# 02_Filtr2.net
KiCad netlist of a schematic drawn in Altium Designer
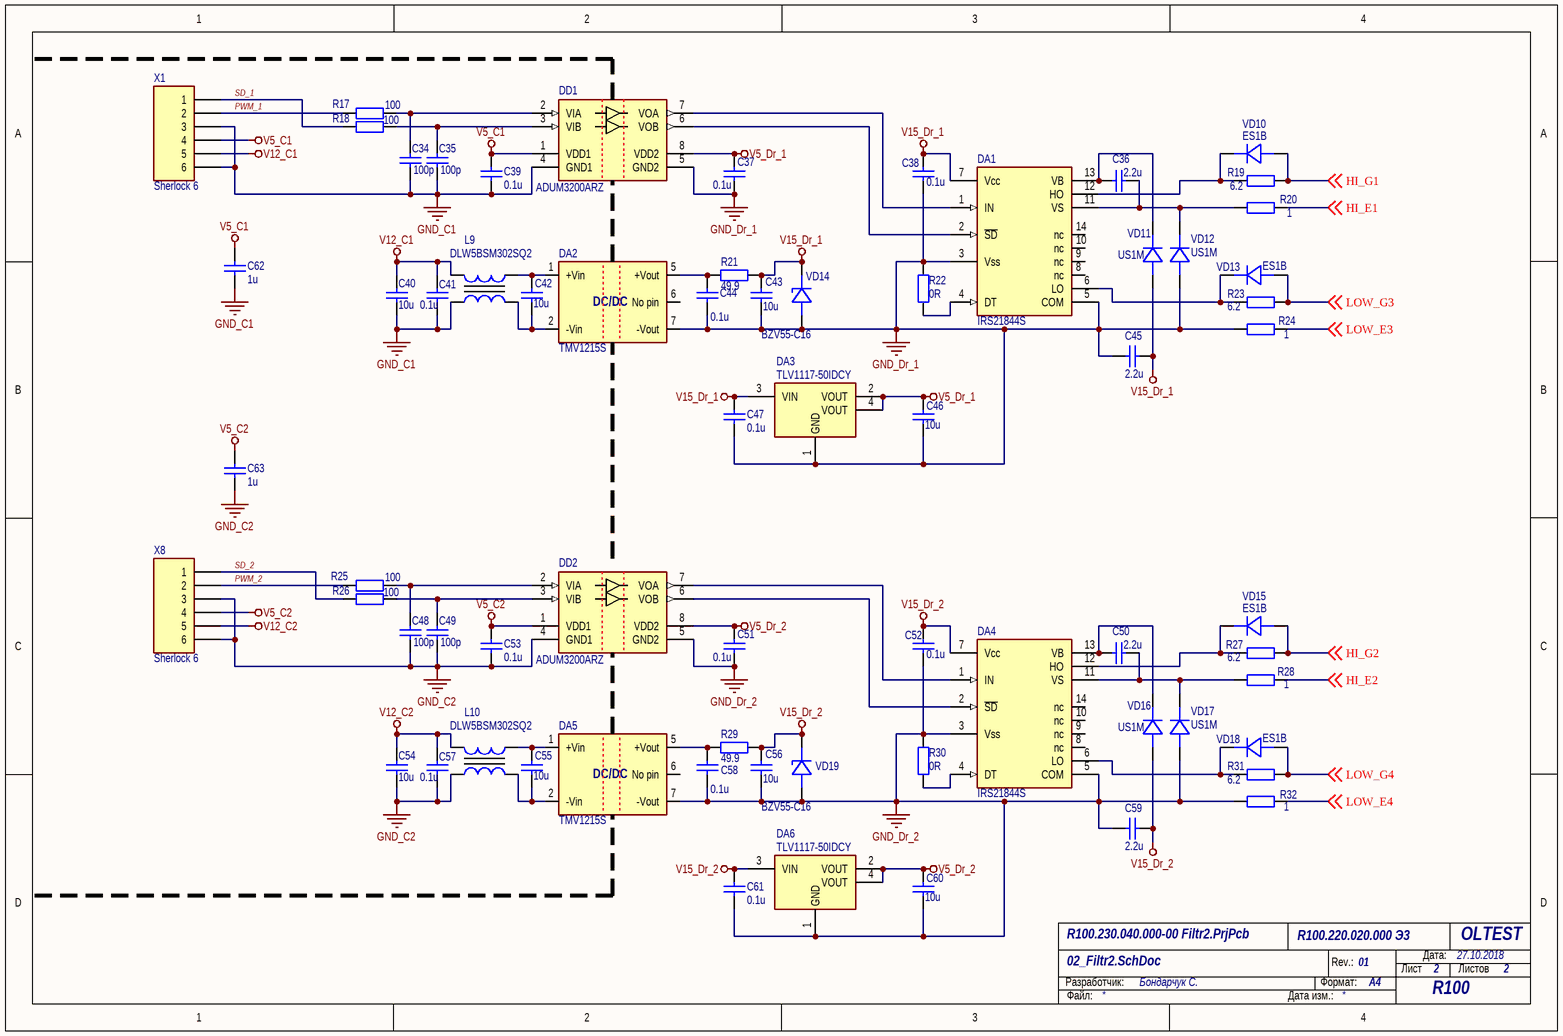
[diagram p0: 02_Filtr2.SchDoc]

(export (version "E")
  (design (tool "Eeschema 10.0.6"))
  (components
    (comp (ref "C34")
      (value "100p")
      (footprint "mainLib:SMD_C_0603")
      (description "SMD C 0603 MURATA 100V 5% NP0")
      (fields (field (name "PARTNUMBER") "GRM1885C2A101JA01") (field (name "MANUFACTURER") "MURATA"))
      (libsource (lib "mainRCLib") (part "C0603 100p 100V 5%"))
    )
    (comp (ref "C35")
      (value "100p")
      (footprint "mainLib:SMD_C_0603")
      (description "SMD C 0603 MURATA 100V 5% NP0")
      (fields (field (name "PARTNUMBER") "GRM1885C2A101JA01") (field (name "MANUFACTURER") "MURATA"))
      (libsource (lib "mainRCLib") (part "C0603 100p 100V 5%"))
    )
    (comp (ref "C36")
      (value "2.2u")
      (footprint "mainLib:SMD_C_1210")
      (description "SMD C 1210 MURATA 100V 10% X7R")
      (fields (field (name "PARTNUMBER") "GRM32ER72A225KA35L") (field (name "MANUFACTURER") "MURATA"))
      (libsource (lib "mainRCLib") (part "C1210 2.2u 100V 10%"))
    )
    (comp (ref "C37")
      (value "0.1u")
      (footprint "mainLib:SMD_C_0603")
      (description "SMD C 0603 MURATA 50V 10% X7R")
      (fields (field (name "PARTNUMBER") "GRM188R71H104K") (field (name "MANUFACTURER") "MURATA"))
      (libsource (lib "mainRCLib") (part "C0603 0.1u 50V 10%"))
    )
    (comp (ref "C38")
      (value "0.1u")
      (footprint "mainLib:SMD_C_0603")
      (description "SMD C 0603 MURATA 50V 10% X7R")
      (fields (field (name "PARTNUMBER") "GRM188R71H104K") (field (name "MANUFACTURER") "MURATA"))
      (libsource (lib "mainRCLib") (part "C0603 0.1u 50V 10%"))
    )
    (comp (ref "C39")
      (value "0.1u")
      (footprint "mainLib:SMD_C_0603")
      (description "SMD C 0603 MURATA 50V 10% X7R")
      (fields (field (name "PARTNUMBER") "GRM188R71H104K") (field (name "MANUFACTURER") "MURATA"))
      (libsource (lib "mainRCLib") (part "C0603 0.1u 50V 10%"))
    )
    (comp (ref "C40")
      (value "10u")
      (footprint "mainLib:SMD_C_1206")
      (description "SMD C 1206 MURATA 25V 20% X5R")
      (fields (field (name "PARTNUMBER") "GRM31MR61E106M") (field (name "MANUFACTURER") "MURATA"))
      (libsource (lib "mainRCLib") (part "C1206 10u 25V 20%"))
    )
    (comp (ref "C41")
      (value "0.1u")
      (footprint "mainLib:SMD_C_0603")
      (description "SMD C 0603 MURATA 50V 10% X7R")
      (fields (field (name "PARTNUMBER") "GRM188R71H104K") (field (name "MANUFACTURER") "MURATA"))
      (libsource (lib "mainRCLib") (part "C0603 0.1u 50V 10%"))
    )
    (comp (ref "C42")
      (value "10u")
      (footprint "mainLib:SMD_C_1206")
      (description "SMD C 1206 MURATA 25V 20% X5R")
      (fields (field (name "PARTNUMBER") "GRM31MR61E106M") (field (name "MANUFACTURER") "MURATA"))
      (libsource (lib "mainRCLib") (part "C1206 10u 25V 20%"))
    )
    (comp (ref "C43")
      (value "10u")
      (footprint "mainLib:SMD_C_1206")
      (description "SMD C 1206 MURATA 25V 20% X5R")
      (fields (field (name "PARTNUMBER") "GRM31MR61E106M") (field (name "MANUFACTURER") "MURATA"))
      (libsource (lib "mainRCLib") (part "C1206 10u 25V 20%"))
    )
    (comp (ref "C44")
      (value "0.1u")
      (footprint "mainLib:SMD_C_0603")
      (description "SMD C 0603 MURATA 50V 10% X7R")
      (fields (field (name "PARTNUMBER") "GRM188R71H104K") (field (name "MANUFACTURER") "MURATA"))
      (libsource (lib "mainRCLib") (part "C0603 0.1u 50V 10%"))
    )
    (comp (ref "C45")
      (value "2.2u")
      (footprint "mainLib:SMD_C_1210")
      (description "SMD C 1210 MURATA 100V 10% X7R")
      (fields (field (name "PARTNUMBER") "GRM32ER72A225KA35L") (field (name "MANUFACTURER") "MURATA"))
      (libsource (lib "mainRCLib") (part "C1210 2.2u 100V 10%"))
    )
    (comp (ref "C46")
      (value "10u")
      (footprint "mainLib:SMD_C_1206")
      (description "SMD C 1206 MURATA 25V 20% X5R")
      (fields (field (name "PARTNUMBER") "GRM31MR61E106M") (field (name "MANUFACTURER") "MURATA"))
      (libsource (lib "mainRCLib") (part "C1206 10u 25V 20%"))
    )
    (comp (ref "C47")
      (value "0.1u")
      (footprint "mainLib:SMD_C_0603")
      (description "SMD C 0603 MURATA 50V 10% X7R")
      (fields (field (name "PARTNUMBER") "GRM188R71H104K") (field (name "MANUFACTURER") "MURATA"))
      (libsource (lib "mainRCLib") (part "C0603 0.1u 50V 10%"))
    )
    (comp (ref "C48")
      (value "100p")
      (footprint "mainLib:SMD_C_0603")
      (description "SMD C 0603 MURATA 100V 5% NP0")
      (fields (field (name "PARTNUMBER") "GRM1885C2A101JA01") (field (name "MANUFACTURER") "MURATA"))
      (libsource (lib "mainRCLib") (part "C0603 100p 100V 5%"))
    )
    (comp (ref "C49")
      (value "100p")
      (footprint "mainLib:SMD_C_0603")
      (description "SMD C 0603 MURATA 100V 5% NP0")
      (fields (field (name "PARTNUMBER") "GRM1885C2A101JA01") (field (name "MANUFACTURER") "MURATA"))
      (libsource (lib "mainRCLib") (part "C0603 100p 100V 5%"))
    )
    (comp (ref "C50")
      (value "2.2u")
      (footprint "mainLib:SMD_C_1210")
      (description "SMD C 1210 MURATA 100V 10% X7R")
      (fields (field (name "PARTNUMBER") "GRM32ER72A225KA35L") (field (name "MANUFACTURER") "MURATA"))
      (libsource (lib "mainRCLib") (part "C1210 2.2u 100V 10%"))
    )
    (comp (ref "C51")
      (value "0.1u")
      (footprint "mainLib:SMD_C_0603")
      (description "SMD C 0603 MURATA 50V 10% X7R")
      (fields (field (name "PARTNUMBER") "GRM188R71H104K") (field (name "MANUFACTURER") "MURATA"))
      (libsource (lib "mainRCLib") (part "C0603 0.1u 50V 10%"))
    )
    (comp (ref "C52")
      (value "0.1u")
      (footprint "mainLib:SMD_C_0603")
      (description "SMD C 0603 MURATA 50V 10% X7R")
      (fields (field (name "PARTNUMBER") "GRM188R71H104K") (field (name "MANUFACTURER") "MURATA"))
      (libsource (lib "mainRCLib") (part "C0603 0.1u 50V 10%"))
    )
    (comp (ref "C53")
      (value "0.1u")
      (footprint "mainLib:SMD_C_0603")
      (description "SMD C 0603 MURATA 50V 10% X7R")
      (fields (field (name "PARTNUMBER") "GRM188R71H104K") (field (name "MANUFACTURER") "MURATA"))
      (libsource (lib "mainRCLib") (part "C0603 0.1u 50V 10%"))
    )
    (comp (ref "C54")
      (value "10u")
      (footprint "mainLib:SMD_C_1206")
      (description "SMD C 1206 MURATA 25V 20% X5R")
      (fields (field (name "PARTNUMBER") "GRM31MR61E106M") (field (name "MANUFACTURER") "MURATA"))
      (libsource (lib "mainRCLib") (part "C1206 10u 25V 20%"))
    )
    (comp (ref "C55")
      (value "10u")
      (footprint "mainLib:SMD_C_1206")
      (description "SMD C 1206 MURATA 25V 20% X5R")
      (fields (field (name "PARTNUMBER") "GRM31MR61E106M") (field (name "MANUFACTURER") "MURATA"))
      (libsource (lib "mainRCLib") (part "C1206 10u 25V 20%"))
    )
    (comp (ref "C56")
      (value "10u")
      (footprint "mainLib:SMD_C_1206")
      (description "SMD C 1206 MURATA 25V 20% X5R")
      (fields (field (name "PARTNUMBER") "GRM31MR61E106M") (field (name "MANUFACTURER") "MURATA"))
      (libsource (lib "mainRCLib") (part "C1206 10u 25V 20%"))
    )
    (comp (ref "C57")
      (value "0.1u")
      (footprint "mainLib:SMD_C_0603")
      (description "SMD C 0603 MURATA 50V 10% X7R")
      (fields (field (name "PARTNUMBER") "GRM188R71H104K") (field (name "MANUFACTURER") "MURATA"))
      (libsource (lib "mainRCLib") (part "C0603 0.1u 50V 10%"))
    )
    (comp (ref "C58")
      (value "0.1u")
      (footprint "mainLib:SMD_C_0603")
      (description "SMD C 0603 MURATA 50V 10% X7R")
      (fields (field (name "PARTNUMBER") "GRM188R71H104K") (field (name "MANUFACTURER") "MURATA"))
      (libsource (lib "mainRCLib") (part "C0603 0.1u 50V 10%"))
    )
    (comp (ref "C59")
      (value "2.2u")
      (footprint "mainLib:SMD_C_1210")
      (description "SMD C 1210 MURATA 100V 10% X7R")
      (fields (field (name "PARTNUMBER") "GRM32ER72A225KA35L") (field (name "MANUFACTURER") "MURATA"))
      (libsource (lib "mainRCLib") (part "C1210 2.2u 100V 10%"))
    )
    (comp (ref "C60")
      (value "10u")
      (footprint "mainLib:SMD_C_1206")
      (description "SMD C 1206 MURATA 25V 20% X5R")
      (fields (field (name "PARTNUMBER") "GRM31MR61E106M") (field (name "MANUFACTURER") "MURATA"))
      (libsource (lib "mainRCLib") (part "C1206 10u 25V 20%"))
    )
    (comp (ref "C61")
      (value "0.1u")
      (footprint "mainLib:SMD_C_0603")
      (description "SMD C 0603 MURATA 50V 10% X7R")
      (fields (field (name "PARTNUMBER") "GRM188R71H104K") (field (name "MANUFACTURER") "MURATA"))
      (libsource (lib "mainRCLib") (part "C0603 0.1u 50V 10%"))
    )
    (comp (ref "C62")
      (value "1u")
      (footprint "mainLib:SMD_C_0603")
      (description "SMD C 0603 MURATA 25V 10% X7R")
      (fields (field (name "PARTNUMBER") "GRM188R71E105KA12") (field (name "MANUFACTURER") "MURATA"))
      (libsource (lib "mainRCLib") (part "C0603 1uF 25V 10%"))
    )
    (comp (ref "C63")
      (value "1u")
      (footprint "mainLib:SMD_C_0603")
      (description "SMD C 0603 MURATA 25V 10% X7R")
      (fields (field (name "PARTNUMBER") "GRM188R71E105KA12") (field (name "MANUFACTURER") "MURATA"))
      (libsource (lib "mainRCLib") (part "C0603 1uF 25V 10%"))
    )
    (comp (ref "DA1")
      (value "IRS21844S")
      (footprint "mainLib:SOIC-14(127P600X175)")
      (description "Half-Bridge Driver")
      (fields
        (field (name "MANUFACTURER") "International Rectifier")
        (field (name "PARTNUMBER") "IRS21844SPBF")
      )
      (libsource (lib "mainLib") (part "IRS21844S"))
    )
    (comp (ref "DA2")
      (value "TMV1215S")
      (footprint "mainLib:SIP7")
      (description "DC/DC")
      (fields (field (name "MANUFACTURER") "TRACO POWER"))
      (libsource (lib "mainLib") (part "TMV1215S"))
    )
    (comp (ref "DA3")
      (value "TLV1117-50IDCY")
      (footprint "mainLib:SOT-223_M")
      (description "Voltage regulator 5.0V 800mA")
      (fields (field (name "MANUFACTURER") "Texas Instrument"))
      (libsource (lib "mainLib") (part "TLV1117-50IDCY"))
    )
    (comp (ref "DA4")
      (value "IRS21844S")
      (footprint "mainLib:SOIC-14(127P600X175)")
      (description "Half-Bridge Driver")
      (fields
        (field (name "MANUFACTURER") "International Rectifier")
        (field (name "PARTNUMBER") "IRS21844SPBF")
      )
      (libsource (lib "mainLib") (part "IRS21844S"))
    )
    (comp (ref "DA5")
      (value "TMV1215S")
      (footprint "mainLib:SIP7")
      (description "DC/DC")
      (fields (field (name "MANUFACTURER") "TRACO POWER"))
      (libsource (lib "mainLib") (part "TMV1215S"))
    )
    (comp (ref "DA6")
      (value "TLV1117-50IDCY")
      (footprint "mainLib:SOT-223_M")
      (description "Voltage regulator 5.0V 800mA")
      (fields (field (name "MANUFACTURER") "Texas Instrument"))
      (libsource (lib "mainLib") (part "TLV1117-50IDCY"))
    )
    (comp (ref "DD1")
      (value "ADUM3200ARZ")
      (footprint "mainLib:SOIC-8")
      (fields (field (name "MANUFACTURER") "Analog Devices"))
      (libsource (lib "mainLib") (part "ADUM3200ARZ"))
    )
    (comp (ref "DD2")
      (value "ADUM3200ARZ")
      (footprint "mainLib:SOIC-8")
      (fields (field (name "MANUFACTURER") "Analog Devices"))
      (libsource (lib "mainLib") (part "ADUM3200ARZ"))
    )
    (comp (ref "L9")
      (value "DLW5BSM302SQ2")
      (footprint "mainLib:DLW5BS(AH)")
      (description "SMD Common Mode Choke Coil 0.5A Z = 3000 Ohm / 100 MHz")
      (fields (field (name "MANUFACTURER") "MURATA"))
      (libsource (lib "mainLib") (part "DLW5BSM302SQ2"))
    )
    (comp (ref "L10")
      (value "DLW5BSM302SQ2")
      (footprint "mainLib:DLW5BS(AH)")
      (description "SMD Common Mode Choke Coil 0.5A Z = 3000 Ohm / 100 MHz")
      (fields (field (name "MANUFACTURER") "MURATA"))
      (libsource (lib "mainLib") (part "DLW5BSM302SQ2"))
    )
    (comp (ref "R17")
      (value "100")
      (footprint "SMD_R_0603")
      (description "SMD R 0603 VISHAY 0.1W 75V 1% 100ppm")
      (fields (field (name "PARTNUMBER") "CRCW0603100RFK") (field (name "MANUFACTURER") "VISHAY"))
      (libsource (lib "mainRCLib") (part "R0603 100 1%"))
    )
    (comp (ref "R18")
      (value "100")
      (footprint "SMD_R_0603")
      (description "SMD R 0603 VISHAY 0.1W 75V 1% 100ppm")
      (fields (field (name "PARTNUMBER") "CRCW0603100RFK") (field (name "MANUFACTURER") "VISHAY"))
      (libsource (lib "mainRCLib") (part "R0603 100 1%"))
    )
    (comp (ref "R19")
      (value "6.2")
      (footprint "mainLib:SMD_R_1206")
      (description "SMD R 1206 VISHAY 0.25W 200V 1% 100ppm")
      (fields (field (name "PARTNUMBER") "CRCW12066R20FK") (field (name "MANUFACTURER") "VISHAY"))
      (libsource (lib "mainRCLib") (part "R1206 6.2 1%"))
    )
    (comp (ref "R20")
      (value "1")
      (footprint "mainLib:SMD_R_1206")
      (description "SMD R 1206 VISHAY 0.25W 200V 1% 100ppm")
      (fields (field (name "PARTNUMBER") "CRCW12061R00FK") (field (name "MANUFACTURER") "VISHAY"))
      (libsource (lib "mainRCLib") (part "R1206 1 1%"))
    )
    (comp (ref "R21")
      (value "49.9")
      (footprint "mainLib:SMD_R_0805")
      (description "SMD R 0805 VISHAY 0.125W 150V 1% 100ppm")
      (fields (field (name "PARTNUMBER") "CRCW080549R9FK") (field (name "MANUFACTURER") "VISHAY"))
      (libsource (lib "mainRCLib") (part "R0805 49.9 1%"))
    )
    (comp (ref "R22")
      (value "0R")
      (footprint "mainLib:SMD_R_0603")
      (description "SMD R 0603 VISHAY 0.1W 75V 1% 100ppm")
      (fields (field (name "PARTNUMBER") "CRCW06030000Z0") (field (name "MANUFACTURER") "VISHAY"))
      (libsource (lib "mainRCLib") (part "R0603 0R 1%"))
    )
    (comp (ref "R23")
      (value "6.2")
      (footprint "mainLib:SMD_R_1206")
      (description "SMD R 1206 VISHAY 0.25W 200V 1% 100ppm")
      (fields (field (name "PARTNUMBER") "CRCW12066R20FK") (field (name "MANUFACTURER") "VISHAY"))
      (libsource (lib "mainRCLib") (part "R1206 6.2 1%"))
    )
    (comp (ref "R24")
      (value "1")
      (footprint "mainLib:SMD_R_1206")
      (description "SMD R 1206 VISHAY 0.25W 200V 1% 100ppm")
      (fields (field (name "PARTNUMBER") "CRCW12061R00FK") (field (name "MANUFACTURER") "VISHAY"))
      (libsource (lib "mainRCLib") (part "R1206 1 1%"))
    )
    (comp (ref "R25")
      (value "100")
      (footprint "SMD_R_0603")
      (description "SMD R 0603 VISHAY 0.1W 75V 1% 100ppm")
      (fields (field (name "PARTNUMBER") "CRCW0603100RFK") (field (name "MANUFACTURER") "VISHAY"))
      (libsource (lib "mainRCLib") (part "R0603 100 1%"))
    )
    (comp (ref "R26")
      (value "100")
      (footprint "SMD_R_0603")
      (description "SMD R 0603 VISHAY 0.1W 75V 1% 100ppm")
      (fields (field (name "PARTNUMBER") "CRCW0603100RFK") (field (name "MANUFACTURER") "VISHAY"))
      (libsource (lib "mainRCLib") (part "R0603 100 1%"))
    )
    (comp (ref "R27")
      (value "6.2")
      (footprint "mainLib:SMD_R_1206")
      (description "SMD R 1206 VISHAY 0.25W 200V 1% 100ppm")
      (fields (field (name "PARTNUMBER") "CRCW12066R20FK") (field (name "MANUFACTURER") "VISHAY"))
      (libsource (lib "mainRCLib") (part "R1206 6.2 1%"))
    )
    (comp (ref "R28")
      (value "1")
      (footprint "mainLib:SMD_R_1206")
      (description "SMD R 1206 VISHAY 0.25W 200V 1% 100ppm")
      (fields (field (name "PARTNUMBER") "CRCW12061R00FK") (field (name "MANUFACTURER") "VISHAY"))
      (libsource (lib "mainRCLib") (part "R1206 1 1%"))
    )
    (comp (ref "R29")
      (value "49.9")
      (footprint "mainLib:SMD_R_0805")
      (description "SMD R 0805 VISHAY 0.125W 150V 1% 100ppm")
      (fields (field (name "PARTNUMBER") "CRCW080549R9FK") (field (name "MANUFACTURER") "VISHAY"))
      (libsource (lib "mainRCLib") (part "R0805 49.9 1%"))
    )
    (comp (ref "R30")
      (value "0R")
      (footprint "mainLib:SMD_R_0603")
      (description "SMD R 0603 VISHAY 0.1W 75V 1% 100ppm")
      (fields (field (name "PARTNUMBER") "CRCW06030000Z0") (field (name "MANUFACTURER") "VISHAY"))
      (libsource (lib "mainRCLib") (part "R0603 0R 1%"))
    )
    (comp (ref "R31")
      (value "6.2")
      (footprint "mainLib:SMD_R_1206")
      (description "SMD R 1206 VISHAY 0.25W 200V 1% 100ppm")
      (fields (field (name "PARTNUMBER") "CRCW12066R20FK") (field (name "MANUFACTURER") "VISHAY"))
      (libsource (lib "mainRCLib") (part "R1206 6.2 1%"))
    )
    (comp (ref "R32")
      (value "1")
      (footprint "mainLib:SMD_R_1206")
      (description "SMD R 1206 VISHAY 0.25W 200V 1% 100ppm")
      (fields (field (name "PARTNUMBER") "CRCW12061R00FK") (field (name "MANUFACTURER") "VISHAY"))
      (libsource (lib "mainRCLib") (part "R1206 1 1%"))
    )
    (comp (ref "VD10")
      (value "ES1B")
      (footprint "mainLib:DO-214AC")
      (description "Vr=100V If=1A Ultrafast")
      (fields (field (name "MANUFACTURER") "Vishay"))
      (libsource (lib "mainLib") (part "ES1B"))
    )
    (comp (ref "VD11")
      (value "US1M")
      (footprint "mainLib:DO-214AC")
      (description "Vr=1000V If=1A Ultrafast")
      (fields (field (name "MANUFACTURER") "Vishay"))
      (libsource (lib "mainLib") (part "US1M"))
    )
    (comp (ref "VD12")
      (value "US1M")
      (footprint "mainLib:DO-214AC")
      (description "Vr=1000V If=1A Ultrafast")
      (fields (field (name "MANUFACTURER") "Vishay"))
      (libsource (lib "mainLib") (part "US1M"))
    )
    (comp (ref "VD13")
      (value "ES1B")
      (footprint "mainLib:DO-214AC")
      (description "Vr=100V If=1A Ultrafast")
      (fields (field (name "MANUFACTURER") "Vishay"))
      (libsource (lib "mainLib") (part "ES1B"))
    )
    (comp (ref "VD14")
      (value "BZV55-C16")
      (footprint "mainLib:SOD80C")
      (description "0.5W Vz=16V +-5%")
      (fields (field (name "MANUFACTURER") "NXP"))
      (libsource (lib "mainLib") (part "BZV55-C16"))
    )
    (comp (ref "VD15")
      (value "ES1B")
      (footprint "mainLib:DO-214AC")
      (description "Vr=100V If=1A Ultrafast")
      (fields (field (name "MANUFACTURER") "Vishay"))
      (libsource (lib "mainLib") (part "ES1B"))
    )
    (comp (ref "VD16")
      (value "US1M")
      (footprint "mainLib:DO-214AC")
      (description "Vr=1000V If=1A Ultrafast")
      (fields (field (name "MANUFACTURER") "Vishay"))
      (libsource (lib "mainLib") (part "US1M"))
    )
    (comp (ref "VD17")
      (value "US1M")
      (footprint "mainLib:DO-214AC")
      (description "Vr=1000V If=1A Ultrafast")
      (fields (field (name "MANUFACTURER") "Vishay"))
      (libsource (lib "mainLib") (part "US1M"))
    )
    (comp (ref "VD18")
      (value "ES1B")
      (footprint "mainLib:DO-214AC")
      (description "Vr=100V If=1A Ultrafast")
      (fields (field (name "MANUFACTURER") "Vishay"))
      (libsource (lib "mainLib") (part "ES1B"))
    )
    (comp (ref "VD19")
      (value "BZV55-C16")
      (footprint "mainLib:SOD80C")
      (description "0.5W Vz=16V +-5%")
      (fields (field (name "MANUFACTURER") "NXP"))
      (libsource (lib "mainLib") (part "BZV55-C16"))
    )
    (comp (ref "X1")
      (value "Sherlock 6")
      (footprint "mainLib:35362-0650")
      (description "Sherlock 6 Side, 2A 125V 2mm")
      (fields (field (name "PARTNUMBER") "35362-0650") (field (name "MANUFACTURER") "MOLEX"))
      (libsource (lib "mainLib") (part "35363-0650"))
    )
    (comp (ref "X8")
      (value "Sherlock 6")
      (footprint "mainLib:35362-0650")
      (description "Sherlock 6 Side, 2A 125V 2mm")
      (fields (field (name "PARTNUMBER") "35362-0650") (field (name "MANUFACTURER") "MOLEX"))
      (libsource (lib "mainLib") (part "35363-0650"))
    )
  )
  (nets
    (net (code "1") (name "/PWM_1") (class "Default")
      (node (ref "R17") (pin "1") (pinfunction "1_1") (pintype "passive"))
      (node (ref "X1") (pin "2") (pinfunction "2_2") (pintype "passive"))
    )
    (net (code "2") (name "/PWM_2") (class "Default")
      (node (ref "R25") (pin "1") (pinfunction "1_1") (pintype "passive"))
      (node (ref "X8") (pin "2") (pinfunction "2_2") (pintype "passive"))
    )
    (net (code "3") (name "/SD_1") (class "Default")
      (node (ref "R18") (pin "1") (pinfunction "1_1") (pintype "passive"))
      (node (ref "X1") (pin "1") (pinfunction "1_1") (pintype "passive"))
    )
    (net (code "4") (name "/SD_2") (class "Default")
      (node (ref "R26") (pin "1") (pinfunction "1_1") (pintype "passive"))
      (node (ref "X8") (pin "1") (pinfunction "1_1") (pintype "passive"))
    )
    (net (code "5") (name "GND_C1") (class "Default")
      (node (ref "C34") (pin "2") (pinfunction "2_2") (pintype "passive"))
      (node (ref "C35") (pin "2") (pinfunction "2_2") (pintype "passive"))
      (node (ref "C39") (pin "1") (pinfunction "1_1") (pintype "passive"))
      (node (ref "C40") (pin "1") (pinfunction "1_1") (pintype "passive"))
      (node (ref "C41") (pin "1") (pinfunction "1_1") (pintype "passive"))
      (node (ref "C62") (pin "2") (pinfunction "2_2") (pintype "passive"))
      (node (ref "DD1") (pin "4") (pinfunction "GND1_4") (pintype "power_in"))
      (node (ref "L9") (pin "4") (pinfunction "4_4") (pintype "passive"))
      (node (ref "X1") (pin "3") (pinfunction "3_3") (pintype "passive"))
      (node (ref "X1") (pin "6") (pinfunction "6_6") (pintype "passive"))
    )
    (net (code "6") (name "GND_C2") (class "Default")
      (node (ref "C48") (pin "2") (pinfunction "2_2") (pintype "passive"))
      (node (ref "C49") (pin "2") (pinfunction "2_2") (pintype "passive"))
      (node (ref "C53") (pin "1") (pinfunction "1_1") (pintype "passive"))
      (node (ref "C54") (pin "1") (pinfunction "1_1") (pintype "passive"))
      (node (ref "C57") (pin "1") (pinfunction "1_1") (pintype "passive"))
      (node (ref "C63") (pin "2") (pinfunction "2_2") (pintype "passive"))
      (node (ref "DD2") (pin "4") (pinfunction "GND1_4") (pintype "power_in"))
      (node (ref "L10") (pin "4") (pinfunction "4_4") (pintype "passive"))
      (node (ref "X8") (pin "3") (pinfunction "3_3") (pintype "passive"))
      (node (ref "X8") (pin "6") (pinfunction "6_6") (pintype "passive"))
    )
    (net (code "7") (name "GND_Dr_1") (class "Default")
      (node (ref "C37") (pin "1") (pinfunction "1_1") (pintype "passive"))
      (node (ref "C38") (pin "2") (pinfunction "2_2") (pintype "passive"))
      (node (ref "C43") (pin "1") (pinfunction "1_1") (pintype "passive"))
      (node (ref "C44") (pin "1") (pinfunction "1_1") (pintype "passive"))
      (node (ref "C45") (pin "2") (pinfunction "2_2") (pintype "passive"))
      (node (ref "C46") (pin "1") (pinfunction "1_1") (pintype "passive"))
      (node (ref "C47") (pin "1") (pinfunction "1_1") (pintype "passive"))
      (node (ref "DA1") (pin "3") (pinfunction "Vss_3") (pintype "power_in"))
      (node (ref "DA1") (pin "5") (pinfunction "COM_5") (pintype "power_in"))
      (node (ref "DA2") (pin "7") (pinfunction "-Vout_7") (pintype "passive"))
      (node (ref "DA3") (pin "1") (pinfunction "GND_1") (pintype "power_in"))
      (node (ref "DD1") (pin "5") (pinfunction "GND2_5") (pintype "power_in"))
      (node (ref "R22") (pin "1") (pinfunction "1_1") (pintype "passive"))
      (node (ref "R24") (pin "1") (pinfunction "1_1") (pintype "passive"))
      (node (ref "VD12") (pin "1") (pinfunction "ANODE_1") (pintype "passive"))
      (node (ref "VD14") (pin "1") (pinfunction "ANODE_1") (pintype "passive"))
    )
    (net (code "8") (name "GND_Dr_2") (class "Default")
      (node (ref "C51") (pin "1") (pinfunction "1_1") (pintype "passive"))
      (node (ref "C52") (pin "2") (pinfunction "2_2") (pintype "passive"))
      (node (ref "C56") (pin "1") (pinfunction "1_1") (pintype "passive"))
      (node (ref "C58") (pin "1") (pinfunction "1_1") (pintype "passive"))
      (node (ref "C59") (pin "2") (pinfunction "2_2") (pintype "passive"))
      (node (ref "C60") (pin "1") (pinfunction "1_1") (pintype "passive"))
      (node (ref "C61") (pin "1") (pinfunction "1_1") (pintype "passive"))
      (node (ref "DA4") (pin "3") (pinfunction "Vss_3") (pintype "power_in"))
      (node (ref "DA4") (pin "5") (pinfunction "COM_5") (pintype "power_in"))
      (node (ref "DA5") (pin "7") (pinfunction "-Vout_7") (pintype "passive"))
      (node (ref "DA6") (pin "1") (pinfunction "GND_1") (pintype "power_in"))
      (node (ref "DD2") (pin "5") (pinfunction "GND2_5") (pintype "power_in"))
      (node (ref "R30") (pin "1") (pinfunction "1_1") (pintype "passive"))
      (node (ref "R32") (pin "1") (pinfunction "1_1") (pintype "passive"))
      (node (ref "VD17") (pin "1") (pinfunction "ANODE_1") (pintype "passive"))
      (node (ref "VD19") (pin "1") (pinfunction "ANODE_1") (pintype "passive"))
    )
    (net (code "9") (name "HI_E1") (class "Default")
      (node (ref "R20") (pin "2") (pinfunction "2_2") (pintype "passive"))
    )
    (net (code "10") (name "HI_E2") (class "Default")
      (node (ref "R28") (pin "2") (pinfunction "2_2") (pintype "passive"))
    )
    (net (code "11") (name "HI_G1") (class "Default")
      (node (ref "R19") (pin "2") (pinfunction "2_2") (pintype "passive"))
      (node (ref "VD10") (pin "1") (pinfunction "ANODE_1") (pintype "passive"))
    )
    (net (code "12") (name "HI_G2") (class "Default")
      (node (ref "R27") (pin "2") (pinfunction "2_2") (pintype "passive"))
      (node (ref "VD15") (pin "1") (pinfunction "ANODE_1") (pintype "passive"))
    )
    (net (code "13") (name "LOW_E3") (class "Default")
      (node (ref "R24") (pin "2") (pinfunction "2_2") (pintype "passive"))
    )
    (net (code "14") (name "LOW_E4") (class "Default")
      (node (ref "R32") (pin "2") (pinfunction "2_2") (pintype "passive"))
    )
    (net (code "15") (name "LOW_G3") (class "Default")
      (node (ref "R23") (pin "2") (pinfunction "2_2") (pintype "passive"))
      (node (ref "VD13") (pin "1") (pinfunction "ANODE_1") (pintype "passive"))
    )
    (net (code "16") (name "LOW_G4") (class "Default")
      (node (ref "R31") (pin "2") (pinfunction "2_2") (pintype "passive"))
      (node (ref "VD18") (pin "1") (pinfunction "ANODE_1") (pintype "passive"))
    )
    (net (code "17") (name "Net-(DA1-DT)") (class "Default")
      (node (ref "DA1") (pin "4") (pinfunction "DT_4") (pintype "input"))
      (node (ref "R22") (pin "2") (pinfunction "2_2") (pintype "passive"))
    )
    (net (code "18") (name "Net-(DA1-HO)") (class "Default")
      (node (ref "DA1") (pin "12") (pinfunction "HO_12") (pintype "passive"))
      (node (ref "R19") (pin "1") (pinfunction "1_1") (pintype "passive"))
      (node (ref "VD10") (pin "2") (pinfunction "CATHODE_2") (pintype "passive"))
    )
    (net (code "19") (name "Net-(DA1-IN)") (class "Default")
      (node (ref "DA1") (pin "1") (pinfunction "IN_1") (pintype "input"))
      (node (ref "DD1") (pin "7") (pinfunction "VOA_7") (pintype "output"))
    )
    (net (code "20") (name "Net-(DA1-LO)") (class "Default")
      (node (ref "DA1") (pin "6") (pinfunction "LO_6") (pintype "passive"))
      (node (ref "R23") (pin "1") (pinfunction "1_1") (pintype "passive"))
      (node (ref "VD13") (pin "2") (pinfunction "CATHODE_2") (pintype "passive"))
    )
    (net (code "21") (name "Net-(DA1-VB)") (class "Default")
      (node (ref "C36") (pin "1") (pinfunction "1_1") (pintype "passive"))
      (node (ref "DA1") (pin "13") (pinfunction "VB_13") (pintype "passive"))
      (node (ref "VD11") (pin "2") (pinfunction "CATHODE_2") (pintype "passive"))
    )
    (net (code "22") (name "Net-(DA1-VS)") (class "Default")
      (node (ref "C36") (pin "2") (pinfunction "2_2") (pintype "passive"))
      (node (ref "DA1") (pin "11") (pinfunction "VS_11") (pintype "passive"))
      (node (ref "R20") (pin "1") (pinfunction "1_1") (pintype "passive"))
      (node (ref "VD12") (pin "2") (pinfunction "CATHODE_2") (pintype "passive"))
    )
    (net (code "23") (name "Net-(DA1-~{SD})") (class "Default")
      (node (ref "DA1") (pin "2") (pinfunction "~{SD}_2") (pintype "input"))
      (node (ref "DD1") (pin "6") (pinfunction "VOB_6") (pintype "output"))
    )
    (net (code "24") (name "Net-(DA2-+Vin)") (class "Default")
      (node (ref "C42") (pin "2") (pinfunction "2_2") (pintype "passive"))
      (node (ref "DA2") (pin "1") (pinfunction "+Vin_1") (pintype "passive"))
      (node (ref "L9") (pin "2") (pinfunction "2_2") (pintype "passive"))
    )
    (net (code "25") (name "Net-(DA2-+Vout)") (class "Default")
      (node (ref "C44") (pin "2") (pinfunction "2_2") (pintype "passive"))
      (node (ref "DA2") (pin "5") (pinfunction "+Vout_5") (pintype "passive"))
      (node (ref "R21") (pin "1") (pinfunction "1_1") (pintype "passive"))
    )
    (net (code "26") (name "Net-(DA2--Vin)") (class "Default")
      (node (ref "C42") (pin "1") (pinfunction "1_1") (pintype "passive"))
      (node (ref "DA2") (pin "2") (pinfunction "-Vin_2") (pintype "passive"))
      (node (ref "L9") (pin "3") (pinfunction "3_3") (pintype "passive"))
    )
    (net (code "27") (name "Net-(DA4-DT)") (class "Default")
      (node (ref "DA4") (pin "4") (pinfunction "DT_4") (pintype "input"))
      (node (ref "R30") (pin "2") (pinfunction "2_2") (pintype "passive"))
    )
    (net (code "28") (name "Net-(DA4-HO)") (class "Default")
      (node (ref "DA4") (pin "12") (pinfunction "HO_12") (pintype "passive"))
      (node (ref "R27") (pin "1") (pinfunction "1_1") (pintype "passive"))
      (node (ref "VD15") (pin "2") (pinfunction "CATHODE_2") (pintype "passive"))
    )
    (net (code "29") (name "Net-(DA4-IN)") (class "Default")
      (node (ref "DA4") (pin "1") (pinfunction "IN_1") (pintype "input"))
      (node (ref "DD2") (pin "7") (pinfunction "VOA_7") (pintype "output"))
    )
    (net (code "30") (name "Net-(DA4-LO)") (class "Default")
      (node (ref "DA4") (pin "6") (pinfunction "LO_6") (pintype "passive"))
      (node (ref "R31") (pin "1") (pinfunction "1_1") (pintype "passive"))
      (node (ref "VD18") (pin "2") (pinfunction "CATHODE_2") (pintype "passive"))
    )
    (net (code "31") (name "Net-(DA4-VB)") (class "Default")
      (node (ref "C50") (pin "1") (pinfunction "1_1") (pintype "passive"))
      (node (ref "DA4") (pin "13") (pinfunction "VB_13") (pintype "passive"))
      (node (ref "VD16") (pin "2") (pinfunction "CATHODE_2") (pintype "passive"))
    )
    (net (code "32") (name "Net-(DA4-VS)") (class "Default")
      (node (ref "C50") (pin "2") (pinfunction "2_2") (pintype "passive"))
      (node (ref "DA4") (pin "11") (pinfunction "VS_11") (pintype "passive"))
      (node (ref "R28") (pin "1") (pinfunction "1_1") (pintype "passive"))
      (node (ref "VD17") (pin "2") (pinfunction "CATHODE_2") (pintype "passive"))
    )
    (net (code "33") (name "Net-(DA4-~{SD})") (class "Default")
      (node (ref "DA4") (pin "2") (pinfunction "~{SD}_2") (pintype "input"))
      (node (ref "DD2") (pin "6") (pinfunction "VOB_6") (pintype "output"))
    )
    (net (code "34") (name "Net-(DA5-+Vin)") (class "Default")
      (node (ref "C55") (pin "2") (pinfunction "2_2") (pintype "passive"))
      (node (ref "DA5") (pin "1") (pinfunction "+Vin_1") (pintype "passive"))
      (node (ref "L10") (pin "2") (pinfunction "2_2") (pintype "passive"))
    )
    (net (code "35") (name "Net-(DA5-+Vout)") (class "Default")
      (node (ref "C58") (pin "2") (pinfunction "2_2") (pintype "passive"))
      (node (ref "DA5") (pin "5") (pinfunction "+Vout_5") (pintype "passive"))
      (node (ref "R29") (pin "1") (pinfunction "1_1") (pintype "passive"))
    )
    (net (code "36") (name "Net-(DA5--Vin)") (class "Default")
      (node (ref "C55") (pin "1") (pinfunction "1_1") (pintype "passive"))
      (node (ref "DA5") (pin "2") (pinfunction "-Vin_2") (pintype "passive"))
      (node (ref "L10") (pin "3") (pinfunction "3_3") (pintype "passive"))
    )
    (net (code "37") (name "Net-(DD1-VIA)") (class "Default")
      (node (ref "C34") (pin "1") (pinfunction "1_1") (pintype "passive"))
      (node (ref "DD1") (pin "2") (pinfunction "VIA_2") (pintype "input"))
      (node (ref "R17") (pin "2") (pinfunction "2_2") (pintype "passive"))
    )
    (net (code "38") (name "Net-(DD1-VIB)") (class "Default")
      (node (ref "C35") (pin "1") (pinfunction "1_1") (pintype "passive"))
      (node (ref "DD1") (pin "3") (pinfunction "VIB_3") (pintype "input"))
      (node (ref "R18") (pin "2") (pinfunction "2_2") (pintype "passive"))
    )
    (net (code "39") (name "Net-(DD2-VIA)") (class "Default")
      (node (ref "C48") (pin "1") (pinfunction "1_1") (pintype "passive"))
      (node (ref "DD2") (pin "2") (pinfunction "VIA_2") (pintype "input"))
      (node (ref "R25") (pin "2") (pinfunction "2_2") (pintype "passive"))
    )
    (net (code "40") (name "Net-(DD2-VIB)") (class "Default")
      (node (ref "C49") (pin "1") (pinfunction "1_1") (pintype "passive"))
      (node (ref "DD2") (pin "3") (pinfunction "VIB_3") (pintype "input"))
      (node (ref "R26") (pin "2") (pinfunction "2_2") (pintype "passive"))
    )
    (net (code "41") (name "V5_C1") (class "Default")
      (node (ref "C39") (pin "2") (pinfunction "2_2") (pintype "passive"))
      (node (ref "C62") (pin "1") (pinfunction "1_1") (pintype "passive"))
      (node (ref "DD1") (pin "1") (pinfunction "VDD1_1") (pintype "power_in"))
      (node (ref "X1") (pin "4") (pinfunction "4_4") (pintype "passive"))
    )
    (net (code "42") (name "V5_C2") (class "Default")
      (node (ref "C53") (pin "2") (pinfunction "2_2") (pintype "passive"))
      (node (ref "C63") (pin "1") (pinfunction "1_1") (pintype "passive"))
      (node (ref "DD2") (pin "1") (pinfunction "VDD1_1") (pintype "power_in"))
      (node (ref "X8") (pin "4") (pinfunction "4_4") (pintype "passive"))
    )
    (net (code "43") (name "V5_Dr_1") (class "Default")
      (node (ref "C37") (pin "2") (pinfunction "2_2") (pintype "passive"))
      (node (ref "C46") (pin "2") (pinfunction "2_2") (pintype "passive"))
      (node (ref "DA3") (pin "2") (pinfunction "VOUT_2") (pintype "power_in"))
      (node (ref "DA3") (pin "4") (pinfunction "VOUT_4") (pintype "power_in"))
      (node (ref "DD1") (pin "8") (pinfunction "VDD2_8") (pintype "power_in"))
    )
    (net (code "44") (name "V5_Dr_2") (class "Default")
      (node (ref "C51") (pin "2") (pinfunction "2_2") (pintype "passive"))
      (node (ref "C60") (pin "2") (pinfunction "2_2") (pintype "passive"))
      (node (ref "DA6") (pin "2") (pinfunction "VOUT_2") (pintype "power_in"))
      (node (ref "DA6") (pin "4") (pinfunction "VOUT_4") (pintype "power_in"))
      (node (ref "DD2") (pin "8") (pinfunction "VDD2_8") (pintype "power_in"))
    )
    (net (code "45") (name "V12_C1") (class "Default")
      (node (ref "C40") (pin "2") (pinfunction "2_2") (pintype "passive"))
      (node (ref "C41") (pin "2") (pinfunction "2_2") (pintype "passive"))
      (node (ref "L9") (pin "1") (pinfunction "1_1") (pintype "passive"))
      (node (ref "X1") (pin "5") (pinfunction "5_5") (pintype "passive"))
    )
    (net (code "46") (name "V12_C2") (class "Default")
      (node (ref "C54") (pin "2") (pinfunction "2_2") (pintype "passive"))
      (node (ref "C57") (pin "2") (pinfunction "2_2") (pintype "passive"))
      (node (ref "L10") (pin "1") (pinfunction "1_1") (pintype "passive"))
      (node (ref "X8") (pin "5") (pinfunction "5_5") (pintype "passive"))
    )
    (net (code "47") (name "V15_Dr_1") (class "Default")
      (node (ref "C38") (pin "1") (pinfunction "1_1") (pintype "passive"))
      (node (ref "C43") (pin "2") (pinfunction "2_2") (pintype "passive"))
      (node (ref "C45") (pin "1") (pinfunction "1_1") (pintype "passive"))
      (node (ref "C47") (pin "2") (pinfunction "2_2") (pintype "passive"))
      (node (ref "DA1") (pin "7") (pinfunction "Vcc_7") (pintype "power_in"))
      (node (ref "DA3") (pin "3") (pinfunction "VIN_3") (pintype "power_in"))
      (node (ref "R21") (pin "2") (pinfunction "2_2") (pintype "passive"))
      (node (ref "VD11") (pin "1") (pinfunction "ANODE_1") (pintype "passive"))
      (node (ref "VD14") (pin "2") (pinfunction "CATHODE_2") (pintype "passive"))
    )
    (net (code "48") (name "V15_Dr_2") (class "Default")
      (node (ref "C52") (pin "1") (pinfunction "1_1") (pintype "passive"))
      (node (ref "C56") (pin "2") (pinfunction "2_2") (pintype "passive"))
      (node (ref "C59") (pin "1") (pinfunction "1_1") (pintype "passive"))
      (node (ref "C61") (pin "2") (pinfunction "2_2") (pintype "passive"))
      (node (ref "DA4") (pin "7") (pinfunction "Vcc_7") (pintype "power_in"))
      (node (ref "DA6") (pin "3") (pinfunction "VIN_3") (pintype "power_in"))
      (node (ref "R29") (pin "2") (pinfunction "2_2") (pintype "passive"))
      (node (ref "VD16") (pin "1") (pinfunction "ANODE_1") (pintype "passive"))
      (node (ref "VD19") (pin "2") (pinfunction "CATHODE_2") (pintype "passive"))
    )
    (net (code "49") (name "unconnected-(DA1-nc-Pad8)") (class "Default")
      (node (ref "DA1") (pin "8") (pinfunction "nc_8") (pintype "passive"))
    )
    (net (code "50") (name "unconnected-(DA1-nc-Pad9)") (class "Default")
      (node (ref "DA1") (pin "9") (pinfunction "nc_9") (pintype "passive"))
    )
    (net (code "51") (name "unconnected-(DA1-nc-Pad10)") (class "Default")
      (node (ref "DA1") (pin "10") (pinfunction "nc_10") (pintype "passive"))
    )
    (net (code "52") (name "unconnected-(DA1-nc-Pad14)") (class "Default")
      (node (ref "DA1") (pin "14") (pinfunction "nc_14") (pintype "passive"))
    )
    (net (code "53") (name "unconnected-(DA2-No_pin-Pad6)") (class "Default")
      (node (ref "DA2") (pin "6") (pinfunction "No_pin_6") (pintype "passive"))
    )
    (net (code "54") (name "unconnected-(DA4-nc-Pad8)") (class "Default")
      (node (ref "DA4") (pin "8") (pinfunction "nc_8") (pintype "passive"))
    )
    (net (code "55") (name "unconnected-(DA4-nc-Pad9)") (class "Default")
      (node (ref "DA4") (pin "9") (pinfunction "nc_9") (pintype "passive"))
    )
    (net (code "56") (name "unconnected-(DA4-nc-Pad10)") (class "Default")
      (node (ref "DA4") (pin "10") (pinfunction "nc_10") (pintype "passive"))
    )
    (net (code "57") (name "unconnected-(DA4-nc-Pad14)") (class "Default")
      (node (ref "DA4") (pin "14") (pinfunction "nc_14") (pintype "passive"))
    )
    (net (code "58") (name "unconnected-(DA5-No_pin-Pad6)") (class "Default")
      (node (ref "DA5") (pin "6") (pinfunction "No_pin_6") (pintype "passive"))
    )
  )
)
